# RF_Power.net
KiCad netlist of a schematic drawn in Altium Designer
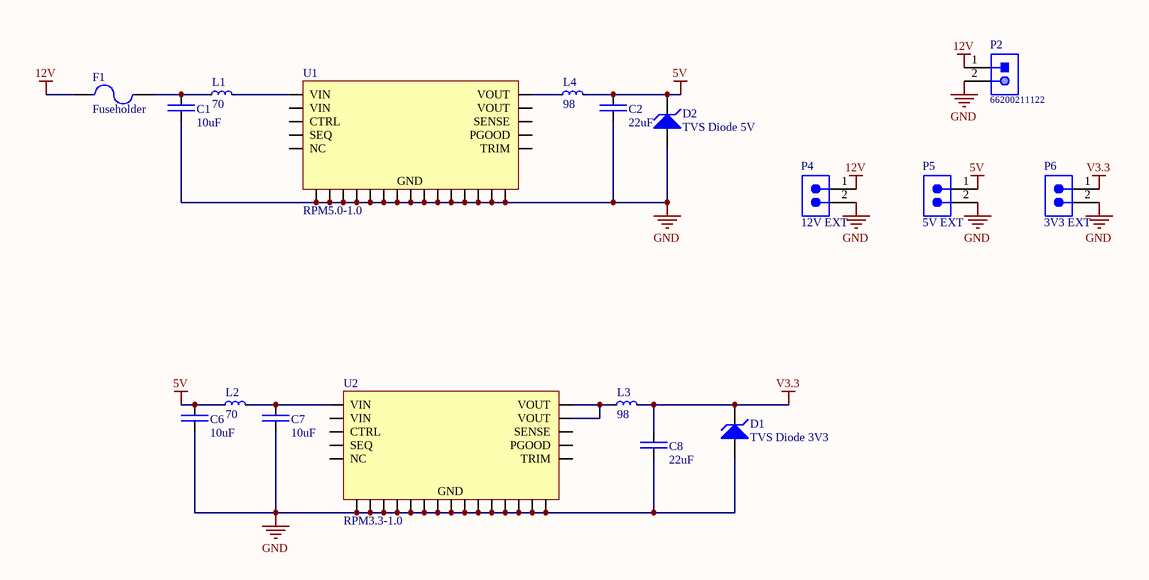
[diagram p0: RF_Power.SchDoc]

(export (version "E")
  (design (tool "Eeschema 10.0.6"))
  (components
    (comp (ref "C1")
      (value "10uF")
      (footprint "1206")
      (description "CAP CER 10UF 25V X7R 1206")
      (fields
        (field (name "MANUFACTURER") "Samsung")
        (field (name "MANUFACTURER PART NUMBER") "CL31B106KAHNFNE")
      )
      (libsource (lib "Capacitors") (part "CL31B106KAHNFNE"))
    )
    (comp (ref "C2")
      (value "22uF")
      (footprint "1206")
      (description "CAP CER 22UF 10V X7R 1206")
      (fields
        (field (name "MANUFACTURER") "Samsung")
        (field (name "MANUFACTURER PART NUMBER") "CL31B226KPHNNNE")
      )
      (libsource (lib "Capacitors") (part "CL31B226KPHNNNE"))
    )
    (comp (ref "C6")
      (value "10uF")
      (footprint "1206")
      (description "CAP CER 10UF 25V X7R 1206")
      (fields
        (field (name "MANUFACTURER") "Samsung")
        (field (name "MANUFACTURER PART NUMBER") "CL31B106KAHNFNE")
      )
      (libsource (lib "Capacitors") (part "CL31B106KAHNFNE"))
    )
    (comp (ref "C7")
      (value "10uF")
      (footprint "1206")
      (description "CAP CER 10UF 25V X7R 1206")
      (fields
        (field (name "MANUFACTURER") "Samsung")
        (field (name "MANUFACTURER PART NUMBER") "CL31B106KAHNFNE")
      )
      (libsource (lib "Capacitors") (part "CL31B106KAHNFNE"))
    )
    (comp (ref "C8")
      (value "22uF")
      (footprint "1206")
      (description "CAP CER 22UF 10V X7R 1206")
      (fields
        (field (name "MANUFACTURER") "Samsung")
        (field (name "MANUFACTURER PART NUMBER") "CL31B226KPHNNNE")
      )
      (libsource (lib "Capacitors") (part "CL31B226KPHNNNE"))
    )
    (comp (ref "D1")
      (value "TVS Diode 3V3")
      (footprint "SOD-323")
      (description "ESD Suppressor TVS ±30kV 2-Pin SOD-323 T/R")
      (fields
        (field (name "MANUFACTURER") "Bourns")
        (field (name "MANUFACTURER PART NUMBER") "CDSOD323-T03S")
      )
      (libsource (lib "Diodes") (part "CDSOD323-T03S"))
    )
    (comp (ref "D2")
      (value "TVS Diode 5V")
      (footprint "SOD-323")
      (description "TVS DIODE 5V 9.8V SOD323")
      (fields
        (field (name "MANUFACTURER") "ON Semiconductor")
        (field (name "MANUFACTURER PART NUMBER") "SD05T1G")
      )
      (libsource (lib "Diodes") (part "SD05T1G"))
    )
    (comp (ref "F1")
      (value "Fuseholder")
      (footprint "SCHURTER - 0031.7701.11 - FUSE HOLDER, PCB MOUNT")
      (description "SCHURTER - 0031.7701.11 - FUSE HOLDER, PCB MOUNT")
      (fields
        (field (name "MANUFACTURER") "Schurter")
        (field (name "MANUFACTURER PART NUMBER") "0031.7701.11")
      )
      (libsource (lib "Fuses & Holders") (part "0031.7701.11"))
    )
    (comp (ref "L1")
      (value "70")
      (footprint "1812")
      (description "WURTH ELEKTRONIK - 742792510 - FERRITE BEAD, 70R, 6A, 1812")
      (fields
        (field (name "MANUFACTURER") "Wurth Electronics")
        (field (name "MANUFACTURER PART NUMBER") "742792510")
      )
      (libsource (lib "Inductors") (part "742792510"))
    )
    (comp (ref "L2")
      (value "70")
      (footprint "1812")
      (description "WURTH ELEKTRONIK - 742792510 - FERRITE BEAD, 70R, 6A, 1812")
      (fields
        (field (name "MANUFACTURER") "Wurth Electronics")
        (field (name "MANUFACTURER PART NUMBER") "742792510")
      )
      (libsource (lib "Inductors") (part "742792510"))
    )
    (comp (ref "L3")
      (value "98")
      (footprint "7427932")
      (description "Ferrite Bead 98 Ohm 2SMD 1LN")
      (fields
        (field (name "MANUFACTURER") "Wurth Electronics")
        (field (name "MANUFACTURER PART NUMBER") "7427932")
      )
      (libsource (lib "Inductors") (part "7427932"))
    )
    (comp (ref "L4")
      (value "98")
      (footprint "7427932")
      (description "Ferrite Bead 98 Ohm 2SMD 1LN")
      (fields
        (field (name "MANUFACTURER") "Wurth Electronics")
        (field (name "MANUFACTURER PART NUMBER") "7427932")
      )
      (libsource (lib "Inductors") (part "7427932"))
    )
    (comp (ref "P2")
      (value "66200211122")
      (footprint "66200211122")
      (description "THT Male Header WR-MPC3, Vertical, Single Row, pitch 3 mm, 2 pins")
      (fields (field (name "MANUFACTURER") "Wurth Elektronik") (field (name "PUBLISHER") "WurthElektronik"))
      (libsource (lib "Altium Content Vault") (part "WE-CN-1P-M-R2"))
    )
    (comp (ref "P4")
      (value "12V EXT")
      (footprint "SMTC-TSW-102-26-XX-S")
      (description "0.025\" SQ Post Header, Through-hole, Vertical, -55 to 125 degC, 2.54 mm Pitch, 2-Pin, Male, RoHS")
      (fields (field (name "PARTNUMBER") "TSW-102-26-G-S") (field (name "MANUFACTURER") "Samtec"))
      (libsource (lib "Altium Content Vault") (part "SMTC-TSW-102-X-X-S-X"))
    )
    (comp (ref "P5")
      (value "5V EXT")
      (footprint "SMTC-TSW-102-26-XX-S")
      (description "0.025\" SQ Post Header, Through-hole, Vertical, -55 to 125 degC, 2.54 mm Pitch, 2-Pin, Male, RoHS")
      (fields (field (name "PARTNUMBER") "TSW-102-26-G-S") (field (name "MANUFACTURER") "Samtec"))
      (libsource (lib "Altium Content Vault") (part "SMTC-TSW-102-X-X-S-X"))
    )
    (comp (ref "P6")
      (value "3V3 EXT")
      (footprint "SMTC-TSW-102-26-XX-S")
      (description "0.025\" SQ Post Header, Through-hole, Vertical, -55 to 125 degC, 2.54 mm Pitch, 2-Pin, Male, RoHS")
      (fields (field (name "PARTNUMBER") "TSW-102-26-G-S") (field (name "MANUFACTURER") "Samtec"))
      (libsource (lib "Altium Content Vault") (part "SMTC-TSW-102-X-X-S-X"))
    )
    (comp (ref "U1")
      (value "RPM5.0-1.0")
      (footprint "25-BLGA")
      (description "1A DC/DC-CONVERTER INNOLINE SM")
      (fields (field (name "MANUFACTURER") "Recom"))
      (libsource (lib "Buck converters & Regulators") (part "RPM5.0-1.0"))
    )
    (comp (ref "U2")
      (value "RPM3.3-1.0")
      (footprint "25-BLGA")
      (description "1A DC/DC-CONVERTER INNOLINE SM")
      (fields (field (name "MANUFACTURER") "Recom"))
      (libsource (lib "Buck converters & Regulators") (part "RPM3.3-1.0"))
    )
  )
  (nets
    (net (code "1") (name "5V") (class "Default")
      (node (ref "C2") (pin "2") (pinfunction "2_2") (pintype "passive"))
      (node (ref "C6") (pin "1") (pinfunction "1_1") (pintype "passive"))
      (node (ref "D2") (pin "2") (pinfunction "K_2") (pintype "passive"))
      (node (ref "L2") (pin "1") (pinfunction "1_1") (pintype "passive"))
      (node (ref "L4") (pin "2") (pinfunction "2_2") (pintype "passive"))
      (node (ref "P5") (pin "1") (pinfunction "1_1") (pintype "passive"))
    )
    (net (code "2") (name "12V") (class "Default")
      (node (ref "F1") (pin "1") (pinfunction "1_1") (pintype "passive"))
      (node (ref "P2") (pin "1") (pinfunction "1_1") (pintype "passive"))
      (node (ref "P4") (pin "1") (pinfunction "1_1") (pintype "passive"))
    )
    (net (code "3") (name "GND") (class "Default")
      (node (ref "C1") (pin "2") (pinfunction "2_2") (pintype "passive"))
      (node (ref "C2") (pin "1") (pinfunction "1_1") (pintype "passive"))
      (node (ref "C6") (pin "2") (pinfunction "2_2") (pintype "passive"))
      (node (ref "C7") (pin "1") (pinfunction "1_1") (pintype "passive"))
      (node (ref "C8") (pin "1") (pinfunction "1_1") (pintype "passive"))
      (node (ref "D1") (pin "1") (pinfunction "A_1") (pintype "passive"))
      (node (ref "D2") (pin "1") (pinfunction "A_1") (pintype "passive"))
      (node (ref "P2") (pin "2") (pinfunction "2_2") (pintype "passive"))
      (node (ref "P4") (pin "2") (pinfunction "2_2") (pintype "passive"))
      (node (ref "P5") (pin "2") (pinfunction "2_2") (pintype "passive"))
      (node (ref "P6") (pin "2") (pinfunction "2_2") (pintype "passive"))
      (node (ref "U1") (pin "A3") (pinfunction "GND_A3") (pintype "passive"))
      (node (ref "U1") (pin "A4") (pinfunction "GND_A4") (pintype "passive"))
      (node (ref "U1") (pin "B1") (pinfunction "GND_B1") (pintype "passive"))
      (node (ref "U1") (pin "B2") (pinfunction "GND_B2") (pintype "passive"))
      (node (ref "U1") (pin "B3") (pinfunction "GND_B3") (pintype "passive"))
      (node (ref "U1") (pin "B4") (pinfunction "GND_B4") (pintype "passive"))
      (node (ref "U1") (pin "C2") (pinfunction "GND_C2") (pintype "passive"))
      (node (ref "U1") (pin "C3") (pinfunction "GND_C3") (pintype "passive"))
      (node (ref "U1") (pin "C4") (pinfunction "GND_C4") (pintype "passive"))
      (node (ref "U1") (pin "D2") (pinfunction "GND_D2") (pintype "passive"))
      (node (ref "U1") (pin "D3") (pinfunction "GND_D3") (pintype "passive"))
      (node (ref "U1") (pin "D4") (pinfunction "GND_D4") (pintype "passive"))
      (node (ref "U1") (pin "D5") (pinfunction "GND_D5") (pintype "passive"))
      (node (ref "U1") (pin "E3") (pinfunction "GND_E3") (pintype "passive"))
      (node (ref "U1") (pin "E4") (pinfunction "GND_E4") (pintype "passive"))
      (node (ref "U2") (pin "A3") (pinfunction "GND_A3") (pintype "passive"))
      (node (ref "U2") (pin "A4") (pinfunction "GND_A4") (pintype "passive"))
      (node (ref "U2") (pin "B1") (pinfunction "GND_B1") (pintype "passive"))
      (node (ref "U2") (pin "B2") (pinfunction "GND_B2") (pintype "passive"))
      (node (ref "U2") (pin "B3") (pinfunction "GND_B3") (pintype "passive"))
      (node (ref "U2") (pin "B4") (pinfunction "GND_B4") (pintype "passive"))
      (node (ref "U2") (pin "C2") (pinfunction "GND_C2") (pintype "passive"))
      (node (ref "U2") (pin "C3") (pinfunction "GND_C3") (pintype "passive"))
      (node (ref "U2") (pin "C4") (pinfunction "GND_C4") (pintype "passive"))
      (node (ref "U2") (pin "D2") (pinfunction "GND_D2") (pintype "passive"))
      (node (ref "U2") (pin "D3") (pinfunction "GND_D3") (pintype "passive"))
      (node (ref "U2") (pin "D4") (pinfunction "GND_D4") (pintype "passive"))
      (node (ref "U2") (pin "D5") (pinfunction "GND_D5") (pintype "passive"))
      (node (ref "U2") (pin "E3") (pinfunction "GND_E3") (pintype "passive"))
      (node (ref "U2") (pin "E4") (pinfunction "GND_E4") (pintype "passive"))
    )
    (net (code "4") (name "Net-(C1-Pad1)") (class "Default")
      (node (ref "C1") (pin "1") (pinfunction "1_1") (pintype "passive"))
      (node (ref "F1") (pin "2") (pinfunction "2_2") (pintype "passive"))
      (node (ref "L1") (pin "1") (pinfunction "1_1") (pintype "passive"))
    )
    (net (code "5") (name "Net-(C7-Pad2)") (class "Default")
      (node (ref "C7") (pin "2") (pinfunction "2_2") (pintype "passive"))
      (node (ref "L2") (pin "2") (pinfunction "2_2") (pintype "passive"))
      (node (ref "U2") (pin "A1") (pinfunction "VIN_A1") (pintype "passive"))
    )
    (net (code "6") (name "Net-(L1-Pad2)") (class "Default")
      (node (ref "L1") (pin "2") (pinfunction "2_2") (pintype "passive"))
      (node (ref "U1") (pin "A1") (pinfunction "VIN_A1") (pintype "passive"))
    )
    (net (code "7") (name "Net-(L3-Pad1)") (class "Default")
      (node (ref "L3") (pin "1") (pinfunction "1_1") (pintype "passive"))
      (node (ref "U2") (pin "A5") (pinfunction "VOUT_A5") (pintype "passive"))
      (node (ref "U2") (pin "B5") (pinfunction "VOUT_B5") (pintype "passive"))
    )
    (net (code "8") (name "Net-(L4-Pad1)") (class "Default")
      (node (ref "L4") (pin "1") (pinfunction "1_1") (pintype "passive"))
      (node (ref "U1") (pin "A5") (pinfunction "VOUT_A5") (pintype "passive"))
    )
    (net (code "9") (name "V3.3") (class "Default")
      (node (ref "C8") (pin "2") (pinfunction "2_2") (pintype "passive"))
      (node (ref "D1") (pin "2") (pinfunction "K_2") (pintype "passive"))
      (node (ref "L3") (pin "2") (pinfunction "2_2") (pintype "passive"))
      (node (ref "P6") (pin "1") (pinfunction "1_1") (pintype "passive"))
    )
    (net (code "10") (name "unconnected-(U1-CTRL-PadC1)") (class "Default")
      (node (ref "U1") (pin "C1") (pinfunction "CTRL_C1") (pintype "passive"))
    )
    (net (code "11") (name "unconnected-(U1-NC-PadE2)") (class "Default")
      (node (ref "U1") (pin "E2") (pinfunction "NC_E2") (pintype "passive"))
    )
    (net (code "12") (name "unconnected-(U1-PGOOD-PadD1)") (class "Default")
      (node (ref "U1") (pin "D1") (pinfunction "PGOOD_D1") (pintype "passive"))
    )
    (net (code "13") (name "unconnected-(U1-SENSE-PadC5)") (class "Default")
      (node (ref "U1") (pin "C5") (pinfunction "SENSE_C5") (pintype "passive"))
    )
    (net (code "14") (name "unconnected-(U1-SEQ-PadE1)") (class "Default")
      (node (ref "U1") (pin "E1") (pinfunction "SEQ_E1") (pintype "passive"))
    )
    (net (code "15") (name "unconnected-(U1-TRIM-PadE5)") (class "Default")
      (node (ref "U1") (pin "E5") (pinfunction "TRIM_E5") (pintype "passive"))
    )
    (net (code "16") (name "unconnected-(U1-VIN-PadA2)") (class "Default")
      (node (ref "U1") (pin "A2") (pinfunction "VIN_A2") (pintype "passive"))
    )
    (net (code "17") (name "unconnected-(U1-VOUT-PadB5)") (class "Default")
      (node (ref "U1") (pin "B5") (pinfunction "VOUT_B5") (pintype "passive"))
    )
    (net (code "18") (name "unconnected-(U2-CTRL-PadC1)") (class "Default")
      (node (ref "U2") (pin "C1") (pinfunction "CTRL_C1") (pintype "passive"))
    )
    (net (code "19") (name "unconnected-(U2-NC-PadE2)") (class "Default")
      (node (ref "U2") (pin "E2") (pinfunction "NC_E2") (pintype "passive"))
    )
    (net (code "20") (name "unconnected-(U2-PGOOD-PadD1)") (class "Default")
      (node (ref "U2") (pin "D1") (pinfunction "PGOOD_D1") (pintype "passive"))
    )
    (net (code "21") (name "unconnected-(U2-SENSE-PadC5)") (class "Default")
      (node (ref "U2") (pin "C5") (pinfunction "SENSE_C5") (pintype "passive"))
    )
    (net (code "22") (name "unconnected-(U2-SEQ-PadE1)") (class "Default")
      (node (ref "U2") (pin "E1") (pinfunction "SEQ_E1") (pintype "passive"))
    )
    (net (code "23") (name "unconnected-(U2-TRIM-PadE5)") (class "Default")
      (node (ref "U2") (pin "E5") (pinfunction "TRIM_E5") (pintype "passive"))
    )
    (net (code "24") (name "unconnected-(U2-VIN-PadA2)") (class "Default")
      (node (ref "U2") (pin "A2") (pinfunction "VIN_A2") (pintype "passive"))
    )
  )
)
